# bias_supply.net
KiCad netlist of a schematic drawn in Altium Designer
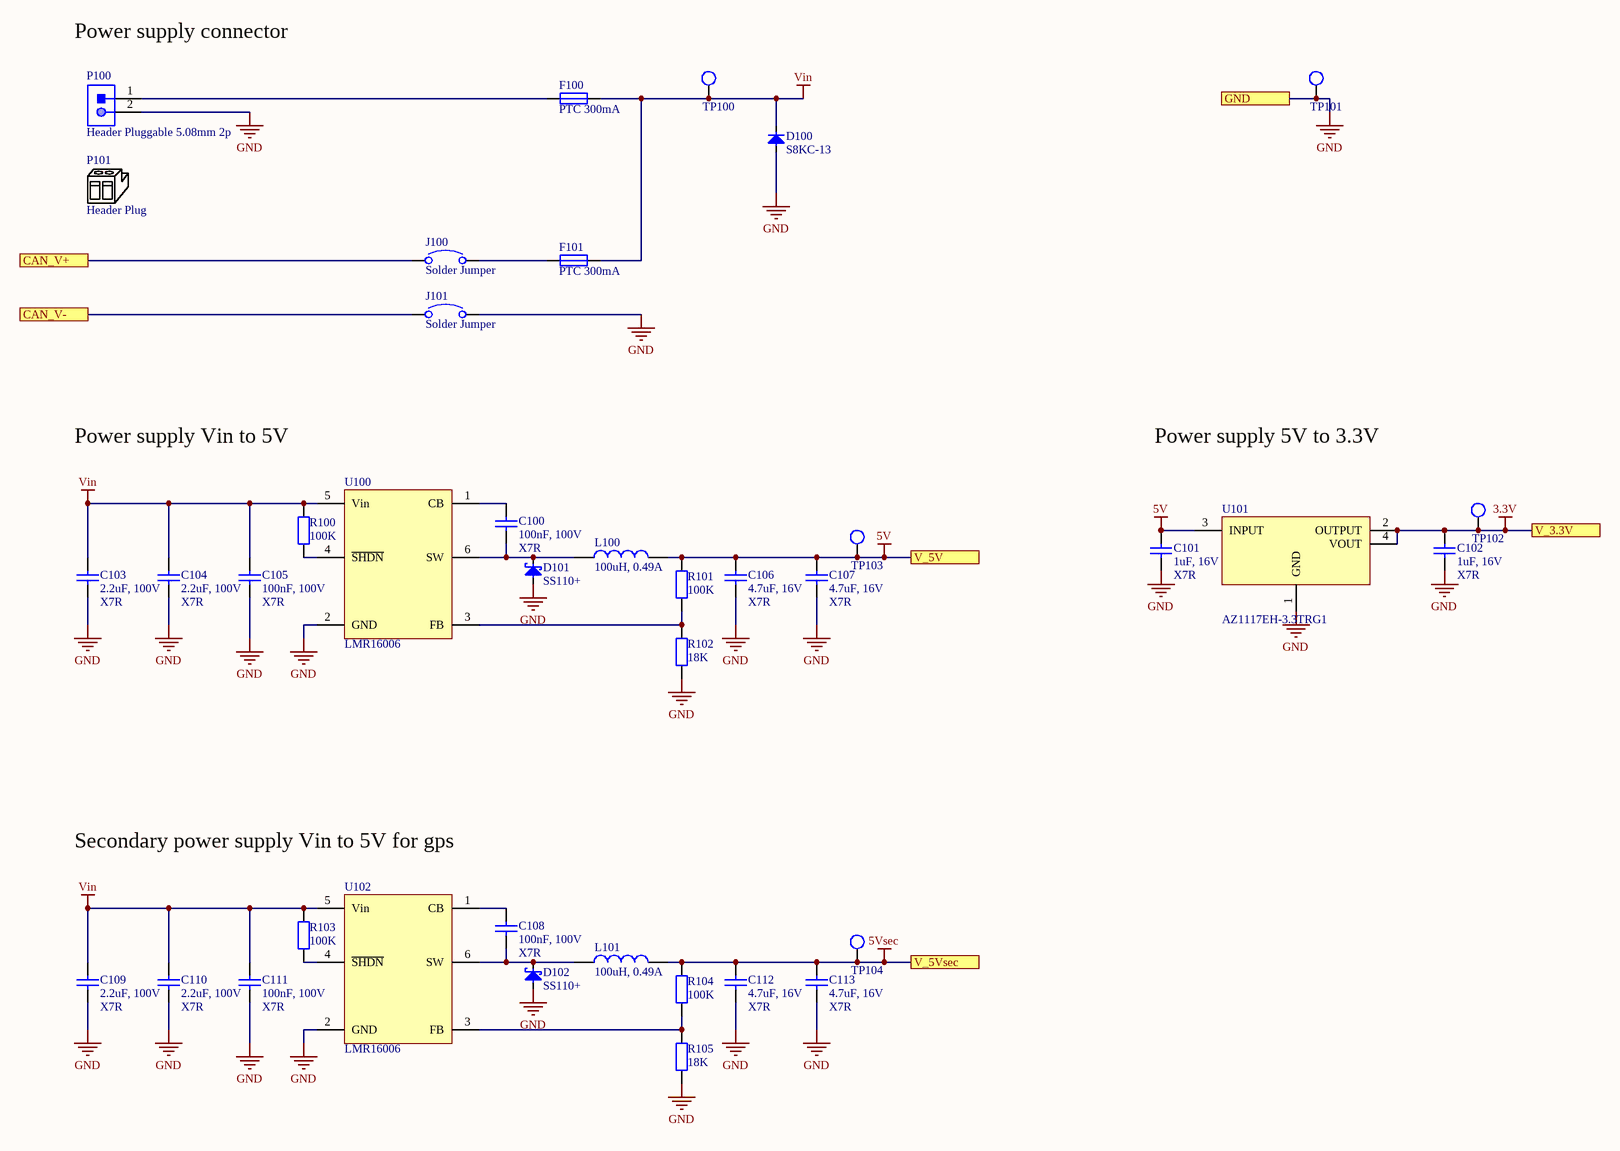
[diagram p0: bias supply.SchDoc]

(export (version "E")
  (design (tool "Eeschema 10.0.6"))
  (components
    (comp (ref "C100")
      (value "100nF, 100V")
      (footprint "CAP_0805")
      (description "WCAP-CSGP Multilayer Ceramic Chip Capacitor, General Purpose, size 0805, X7R, 100nF, 100V")
      (fields
        (field (name "MANUFACTURER PART NUMBER") "885012207128")
        (field (name "MANUFACTURER") "Wurth Elektronik")
        (field (name "CERAMIC TYPE") "X7R")
      )
      (libsource (lib "004-H-01 SD data logger") (part "CAP_0805_100nF_100V"))
    )
    (comp (ref "C101")
      (value "1uF, 16V")
      (footprint "CAP_0805")
      (description "WCAP-CSGP Multilayer Ceramic Chip Capacitor, General Purpose, size 0805, X7R, 1uF, 16V")
      (fields
        (field (name "MANUFACTURER PART NUMBER") "885012207051")
        (field (name "MANUFACTURER") "Wurth Elektronik")
        (field (name "CERAMIC TYPE") "X7R")
      )
      (libsource (lib "004-H-01 SD data logger") (part "CAP_0805_1uF_16V"))
    )
    (comp (ref "C102")
      (value "1uF, 16V")
      (footprint "CAP_0805")
      (description "WCAP-CSGP Multilayer Ceramic Chip Capacitor, General Purpose, size 0805, X7R, 1uF, 16V")
      (fields
        (field (name "MANUFACTURER PART NUMBER") "885012207051")
        (field (name "MANUFACTURER") "Wurth Elektronik")
        (field (name "CERAMIC TYPE") "X7R")
      )
      (libsource (lib "004-H-01 SD data logger") (part "CAP_0805_1uF_16V"))
    )
    (comp (ref "C103")
      (value "2.2uF, 100V")
      (footprint "CAP_1210")
      (description "WCAP-CSGP Multilayer Ceramic Chip Capacitor, General Purpose, size 1210, X7R, 2.2uF, 100V")
      (fields
        (field (name "MANUFACTURER PART NUMBER") "885012209071")
        (field (name "MANUFACTURER") "Wurth Elektronik")
        (field (name "CERAMIC TYPE") "X7R")
      )
      (libsource (lib "004-H-01 SD data logger") (part "CAP_1210_2.2uF_100V"))
    )
    (comp (ref "C104")
      (value "2.2uF, 100V")
      (footprint "CAP_1210")
      (description "WCAP-CSGP Multilayer Ceramic Chip Capacitor, General Purpose, size 1210, X7R, 2.2uF, 100V")
      (fields
        (field (name "MANUFACTURER PART NUMBER") "885012209071")
        (field (name "MANUFACTURER") "Wurth Elektronik")
        (field (name "CERAMIC TYPE") "X7R")
      )
      (libsource (lib "004-H-01 SD data logger") (part "CAP_1210_2.2uF_100V"))
    )
    (comp (ref "C105")
      (value "100nF, 100V")
      (footprint "CAP_0805")
      (description "WCAP-CSGP Multilayer Ceramic Chip Capacitor, General Purpose, size 0805, X7R, 100nF, 100V")
      (fields
        (field (name "MANUFACTURER PART NUMBER") "885012207128")
        (field (name "MANUFACTURER") "Wurth Elektronik")
        (field (name "CERAMIC TYPE") "X7R")
      )
      (libsource (lib "004-H-01 SD data logger") (part "CAP_0805_100nF_100V"))
    )
    (comp (ref "C106")
      (value "4.7uF, 16V")
      (footprint "CAP_0805")
      (description "WCAP-CSGP Multilayer Ceramic Chip Capacitor, General Purpose, size 0805, X7R, 4.7uF, 16V")
      (fields
        (field (name "MANUFACTURER PART NUMBER") "885012207053")
        (field (name "MANUFACTURER") "Wurth Elektronik")
        (field (name "CERAMIC TYPE") "X7R")
      )
      (libsource (lib "004-H-01 SD data logger") (part "CAP_0805_4.7uF_16V"))
    )
    (comp (ref "C107")
      (value "4.7uF, 16V")
      (footprint "CAP_0805")
      (description "WCAP-CSGP Multilayer Ceramic Chip Capacitor, General Purpose, size 0805, X7R, 4.7uF, 16V")
      (fields
        (field (name "MANUFACTURER PART NUMBER") "885012207053")
        (field (name "MANUFACTURER") "Wurth Elektronik")
        (field (name "CERAMIC TYPE") "X7R")
      )
      (libsource (lib "004-H-01 SD data logger") (part "CAP_0805_4.7uF_16V"))
    )
    (comp (ref "C108")
      (value "100nF, 100V")
      (footprint "CAP_0805")
      (description "WCAP-CSGP Multilayer Ceramic Chip Capacitor, General Purpose, size 0805, X7R, 100nF, 100V")
      (fields
        (field (name "MANUFACTURER PART NUMBER") "885012207128")
        (field (name "MANUFACTURER") "Wurth Elektronik")
        (field (name "CERAMIC TYPE") "X7R")
      )
      (libsource (lib "004-H-01 SD data logger") (part "CAP_0805_100nF_100V"))
    )
    (comp (ref "C109")
      (value "2.2uF, 100V")
      (footprint "CAP_1210")
      (description "WCAP-CSGP Multilayer Ceramic Chip Capacitor, General Purpose, size 1210, X7R, 2.2uF, 100V")
      (fields
        (field (name "MANUFACTURER PART NUMBER") "885012209071")
        (field (name "MANUFACTURER") "Wurth Elektronik")
        (field (name "CERAMIC TYPE") "X7R")
      )
      (libsource (lib "004-H-01 SD data logger") (part "CAP_1210_2.2uF_100V"))
    )
    (comp (ref "C110")
      (value "2.2uF, 100V")
      (footprint "CAP_1210")
      (description "WCAP-CSGP Multilayer Ceramic Chip Capacitor, General Purpose, size 1210, X7R, 2.2uF, 100V")
      (fields
        (field (name "MANUFACTURER PART NUMBER") "885012209071")
        (field (name "MANUFACTURER") "Wurth Elektronik")
        (field (name "CERAMIC TYPE") "X7R")
      )
      (libsource (lib "004-H-01 SD data logger") (part "CAP_1210_2.2uF_100V"))
    )
    (comp (ref "C111")
      (value "100nF, 100V")
      (footprint "CAP_0805")
      (description "WCAP-CSGP Multilayer Ceramic Chip Capacitor, General Purpose, size 0805, X7R, 100nF, 100V")
      (fields
        (field (name "MANUFACTURER PART NUMBER") "885012207128")
        (field (name "MANUFACTURER") "Wurth Elektronik")
        (field (name "CERAMIC TYPE") "X7R")
      )
      (libsource (lib "004-H-01 SD data logger") (part "CAP_0805_100nF_100V"))
    )
    (comp (ref "C112")
      (value "4.7uF, 16V")
      (footprint "CAP_0805")
      (description "WCAP-CSGP Multilayer Ceramic Chip Capacitor, General Purpose, size 0805, X7R, 4.7uF, 16V")
      (fields
        (field (name "MANUFACTURER PART NUMBER") "885012207053")
        (field (name "MANUFACTURER") "Wurth Elektronik")
        (field (name "CERAMIC TYPE") "X7R")
      )
      (libsource (lib "004-H-01 SD data logger") (part "CAP_0805_4.7uF_16V"))
    )
    (comp (ref "C113")
      (value "4.7uF, 16V")
      (footprint "CAP_0805")
      (description "WCAP-CSGP Multilayer Ceramic Chip Capacitor, General Purpose, size 0805, X7R, 4.7uF, 16V")
      (fields
        (field (name "MANUFACTURER PART NUMBER") "885012207053")
        (field (name "MANUFACTURER") "Wurth Elektronik")
        (field (name "CERAMIC TYPE") "X7R")
      )
      (libsource (lib "004-H-01 SD data logger") (part "CAP_0805_4.7uF_16V"))
    )
    (comp (ref "D100")
      (value "S8KC-13")
      (footprint "DIODEDO-214AB")
      (description "Diode")
      (fields (field (name "MANUFACTURER") "Diodes inc"))
      (libsource (lib "004-H-01 SD data logger") (part "Diode S8KC-13"))
    )
    (comp (ref "D101")
      (value "SS110+")
      (footprint "DIODEDO-214AC")
      (description "Diode Schottky")
      (fields (field (name "MANUFACTURER") "Multicomp"))
      (libsource (lib "004-H-01 SD data logger") (part "Diode Schottky SS110+"))
    )
    (comp (ref "D102")
      (value "SS110+")
      (footprint "DIODEDO-214AC")
      (description "Diode Schottky")
      (fields (field (name "MANUFACTURER") "Multicomp"))
      (libsource (lib "004-H-01 SD data logger") (part "Diode Schottky SS110+"))
    )
    (comp (ref "F100")
      (value "PTC 300mA")
      (footprint "PTC7451X12N")
      (description "Fuse")
      (fields (field (name "MANUFACTURER") "Multicomp Pro") (field (name "MANUFACTURER PART NO") "MC33189"))
      (libsource (lib "004-H-01 SD data logger") (part "PTC 300mA"))
    )
    (comp (ref "F101")
      (value "PTC 300mA")
      (footprint "PTC7451X12N")
      (description "Fuse")
      (fields (field (name "MANUFACTURER") "Multicomp Pro") (field (name "MANUFACTURER PART NO") "MC33189"))
      (libsource (lib "004-H-01 SD data logger") (part "PTC 300mA"))
    )
    (comp (ref "J100")
      (value "Solder Jumper")
      (footprint "SolderJumer")
      (description "Solder jumper open")
      (libsource (lib "004-H-01 SD data logger") (part "SolderJumper"))
    )
    (comp (ref "J101")
      (value "Solder Jumper")
      (footprint "SolderJumer")
      (description "Solder jumper open")
      (libsource (lib "004-H-01 SD data logger") (part "SolderJumper"))
    )
    (comp (ref "L100")
      (value "100uH, 0.49A")
      (footprint "WE-LQS_4025")
      (description "WE-LQS SMT Power Inductor, size 4025, 100uH, 0.49A")
      (fields
        (field (name "MANUFACTURER") "Wurth Elektronik")
        (field (name "MANUFACTURER PART NUMBER") "74404043101A")
      )
      (libsource (lib "004-H-01 SD data logger") (part "Inductor 100uH 0.49A 1043mOhm"))
    )
    (comp (ref "L101")
      (value "100uH, 0.49A")
      (footprint "WE-LQS_4025")
      (description "WE-LQS SMT Power Inductor, size 4025, 100uH, 0.49A")
      (fields
        (field (name "MANUFACTURER") "Wurth Elektronik")
        (field (name "MANUFACTURER PART NUMBER") "74404043101A")
      )
      (libsource (lib "004-H-01 SD data logger") (part "Inductor 100uH 0.49A 1043mOhm"))
    )
    (comp (ref "P100")
      (value "Header Pluggable 5.08mm 2p")
      (footprint "WE-691313510002")
      (description "WR-TBL Serie 313 Close Horizontal PCB Header, Pluggable, pitch 5.08mm, 2p")
      (fields (field (name "PART NUMBER") "691313510002") (field (name "PUBLISHER") "Wurth Elektronik"))
      (libsource (lib "004-H-01 SD data logger") (part "Header Pluggable 5.08mm 2p"))
    )
    (comp (ref "P101")
      (value "Header Plug")
      (description "WR-TBL Series 351 - 5.08 mm Vertical, pitch 5.08mm, 2p")
      (fields (field (name "PART NUMBER") "691351500002") (field (name "PUBLISHER") "Wurth Elektronik"))
      (libsource (lib "004-H-01 SD data logger") (part "Plug Pluggable 5.08mm 2p"))
    )
    (comp (ref "R100")
      (value "100K")
      (footprint "RES_0805")
      (description "Thick Film Resistor, size 0805, 1%")
      (libsource (lib "004-H-01 SD data logger") (part "RES_0805_100K"))
    )
    (comp (ref "R101")
      (value "100K")
      (footprint "RES_0805")
      (description "Thick Film Resistor, size 0805, 1%")
      (libsource (lib "004-H-01 SD data logger") (part "RES_0805_100K"))
    )
    (comp (ref "R102")
      (value "18K")
      (footprint "RES_0805")
      (description "Thick Film Resistor, size 0805, 1%")
      (libsource (lib "004-H-01 SD data logger") (part "RES_0805_18K"))
    )
    (comp (ref "R103")
      (value "100K")
      (footprint "RES_0805")
      (description "Thick Film Resistor, size 0805, 1%")
      (libsource (lib "004-H-01 SD data logger") (part "RES_0805_100K"))
    )
    (comp (ref "R104")
      (value "100K")
      (footprint "RES_0805")
      (description "Thick Film Resistor, size 0805, 1%")
      (libsource (lib "004-H-01 SD data logger") (part "RES_0805_100K"))
    )
    (comp (ref "R105")
      (value "18K")
      (footprint "RES_0805")
      (description "Thick Film Resistor, size 0805, 1%")
      (libsource (lib "004-H-01 SD data logger") (part "RES_0805_18K"))
    )
    (comp (ref "TP100")
      (value "Test Pad")
      (footprint "TestPad")
      (description "Test pad 2mm")
      (libsource (lib "004-H-01 SD data logger") (part "Test Pad"))
    )
    (comp (ref "TP101")
      (value "Test Pad")
      (footprint "TestPad")
      (description "Test pad 2mm")
      (libsource (lib "004-H-01 SD data logger") (part "Test Pad"))
    )
    (comp (ref "TP102")
      (value "Test Pad")
      (footprint "TestPad")
      (description "Test pad 2mm")
      (libsource (lib "004-H-01 SD data logger") (part "Test Pad"))
    )
    (comp (ref "TP103")
      (value "Test Pad")
      (footprint "TestPad")
      (description "Test pad 2mm")
      (libsource (lib "004-H-01 SD data logger") (part "Test Pad"))
    )
    (comp (ref "TP104")
      (value "Test Pad")
      (footprint "TestPad")
      (description "Test pad 2mm")
      (libsource (lib "004-H-01 SD data logger") (part "Test Pad"))
    )
    (comp (ref "U100")
      (value "LMR16006")
      (footprint "SOT95P280X110-6N")
      (fields
        (field (name "MANUFACTURER") "Texas Instruments")
        (field (name "MANUFACTURER PART NO") "LMR16006XDDCT")
      )
      (libsource (lib "004-H-01 SD data logger") (part "LMR16006"))
    )
    (comp (ref "U101")
      (value "AZ1117EH-3.3TRG1")
      (footprint "FP-SOT223-IPC_A")
      (description "IC REG LINEAR 3.3V 1A SOT223")
      (fields (field (name "MANUFACTURER") "Diodes Inc"))
      (libsource (lib "004-H-01 SD data logger") (part "AZ1117EH-3.3TRG1"))
    )
    (comp (ref "U102")
      (value "LMR16006")
      (footprint "SOT95P280X110-6N")
      (fields
        (field (name "MANUFACTURER") "Texas Instruments")
        (field (name "MANUFACTURER PART NO") "LMR16006XDDCT")
      )
      (libsource (lib "004-H-01 SD data logger") (part "LMR16006"))
    )
  )
  (nets
    (net (code "1") (name "/CAN_V+") (class "Default")
      (node (ref "J100") (pin "1") (pinfunction "1_1") (pintype "passive"))
    )
    (net (code "2") (name "/CAN_V-") (class "Default")
      (node (ref "J101") (pin "1") (pinfunction "1_1") (pintype "passive"))
    )
    (net (code "3") (name "3.3V") (class "Default")
      (node (ref "C102") (pin "1") (pinfunction "1_1") (pintype "passive"))
      (node (ref "TP102") (pin "1") (pinfunction "1_1") (pintype "passive"))
      (node (ref "U101") (pin "2") (pinfunction "OUTPUT_2") (pintype "power_in"))
      (node (ref "U101") (pin "4") (pinfunction "VOUT_4") (pintype "power_in"))
    )
    (net (code "4") (name "5V") (class "Default")
      (node (ref "C101") (pin "2") (pinfunction "2_2") (pintype "passive"))
      (node (ref "C106") (pin "2") (pinfunction "2_2") (pintype "passive"))
      (node (ref "C107") (pin "1") (pinfunction "1_1") (pintype "passive"))
      (node (ref "L100") (pin "2") (pinfunction "2_2") (pintype "passive"))
      (node (ref "R101") (pin "2") (pinfunction "2_2") (pintype "passive"))
      (node (ref "TP103") (pin "1") (pinfunction "1_1") (pintype "passive"))
      (node (ref "U101") (pin "3") (pinfunction "INPUT_3") (pintype "power_in"))
    )
    (net (code "5") (name "5Vsec") (class "Default")
      (node (ref "C112") (pin "2") (pinfunction "2_2") (pintype "passive"))
      (node (ref "C113") (pin "1") (pinfunction "1_1") (pintype "passive"))
      (node (ref "L101") (pin "2") (pinfunction "2_2") (pintype "passive"))
      (node (ref "R104") (pin "2") (pinfunction "2_2") (pintype "passive"))
      (node (ref "TP104") (pin "1") (pinfunction "1_1") (pintype "passive"))
    )
    (net (code "6") (name "GND") (class "Default")
      (node (ref "C101") (pin "1") (pinfunction "1_1") (pintype "passive"))
      (node (ref "C102") (pin "2") (pinfunction "2_2") (pintype "passive"))
      (node (ref "C103") (pin "1") (pinfunction "1_1") (pintype "passive"))
      (node (ref "C104") (pin "2") (pinfunction "2_2") (pintype "passive"))
      (node (ref "C105") (pin "1") (pinfunction "1_1") (pintype "passive"))
      (node (ref "C106") (pin "1") (pinfunction "1_1") (pintype "passive"))
      (node (ref "C107") (pin "2") (pinfunction "2_2") (pintype "passive"))
      (node (ref "C109") (pin "1") (pinfunction "1_1") (pintype "passive"))
      (node (ref "C110") (pin "2") (pinfunction "2_2") (pintype "passive"))
      (node (ref "C111") (pin "1") (pinfunction "1_1") (pintype "passive"))
      (node (ref "C112") (pin "1") (pinfunction "1_1") (pintype "passive"))
      (node (ref "C113") (pin "2") (pinfunction "2_2") (pintype "passive"))
      (node (ref "D100") (pin "2") (pinfunction "A_2") (pintype "passive"))
      (node (ref "D101") (pin "2") (pinfunction "A_2") (pintype "passive"))
      (node (ref "D102") (pin "2") (pinfunction "A_2") (pintype "passive"))
      (node (ref "J101") (pin "2") (pinfunction "2_2") (pintype "passive"))
      (node (ref "P100") (pin "2") (pinfunction "2_2") (pintype "passive"))
      (node (ref "R102") (pin "1") (pinfunction "1_1") (pintype "passive"))
      (node (ref "R105") (pin "1") (pinfunction "1_1") (pintype "passive"))
      (node (ref "TP101") (pin "1") (pinfunction "1_1") (pintype "passive"))
      (node (ref "U100") (pin "2") (pinfunction "GND_2") (pintype "passive"))
      (node (ref "U101") (pin "1") (pinfunction "GND_1") (pintype "power_in"))
      (node (ref "U102") (pin "2") (pinfunction "GND_2") (pintype "passive"))
    )
    (net (code "7") (name "Net-(D101-K)") (class "Default")
      (node (ref "C100") (pin "2") (pinfunction "2_2") (pintype "passive"))
      (node (ref "D101") (pin "1") (pinfunction "K_1") (pintype "passive"))
      (node (ref "L100") (pin "1") (pinfunction "1_1") (pintype "passive"))
      (node (ref "U100") (pin "6") (pinfunction "SW_6") (pintype "passive"))
    )
    (net (code "8") (name "Net-(D102-K)") (class "Default")
      (node (ref "C108") (pin "2") (pinfunction "2_2") (pintype "passive"))
      (node (ref "D102") (pin "1") (pinfunction "K_1") (pintype "passive"))
      (node (ref "L101") (pin "1") (pinfunction "1_1") (pintype "passive"))
      (node (ref "U102") (pin "6") (pinfunction "SW_6") (pintype "passive"))
    )
    (net (code "9") (name "Net-(F100-Pad1)") (class "Default")
      (node (ref "F100") (pin "1") (pinfunction "1_1") (pintype "passive"))
      (node (ref "P100") (pin "1") (pinfunction "1_1") (pintype "passive"))
    )
    (net (code "10") (name "Net-(F101-Pad1)") (class "Default")
      (node (ref "F101") (pin "1") (pinfunction "1_1") (pintype "passive"))
      (node (ref "J100") (pin "2") (pinfunction "2_2") (pintype "passive"))
    )
    (net (code "11") (name "Net-(U100-CB)") (class "Default")
      (node (ref "C100") (pin "1") (pinfunction "1_1") (pintype "passive"))
      (node (ref "U100") (pin "1") (pinfunction "CB_1") (pintype "passive"))
    )
    (net (code "12") (name "Net-(U100-FB)") (class "Default")
      (node (ref "R101") (pin "1") (pinfunction "1_1") (pintype "passive"))
      (node (ref "R102") (pin "2") (pinfunction "2_2") (pintype "passive"))
      (node (ref "U100") (pin "3") (pinfunction "FB_3") (pintype "passive"))
    )
    (net (code "13") (name "Net-(U100-~{SHDN})") (class "Default")
      (node (ref "R100") (pin "1") (pinfunction "1_1") (pintype "passive"))
      (node (ref "U100") (pin "4") (pinfunction "~{SHDN}_4") (pintype "passive"))
    )
    (net (code "14") (name "Net-(U102-CB)") (class "Default")
      (node (ref "C108") (pin "1") (pinfunction "1_1") (pintype "passive"))
      (node (ref "U102") (pin "1") (pinfunction "CB_1") (pintype "passive"))
    )
    (net (code "15") (name "Net-(U102-FB)") (class "Default")
      (node (ref "R104") (pin "1") (pinfunction "1_1") (pintype "passive"))
      (node (ref "R105") (pin "2") (pinfunction "2_2") (pintype "passive"))
      (node (ref "U102") (pin "3") (pinfunction "FB_3") (pintype "passive"))
    )
    (net (code "16") (name "Net-(U102-~{SHDN})") (class "Default")
      (node (ref "R103") (pin "1") (pinfunction "1_1") (pintype "passive"))
      (node (ref "U102") (pin "4") (pinfunction "~{SHDN}_4") (pintype "passive"))
    )
    (net (code "17") (name "Vin") (class "Default")
      (node (ref "C103") (pin "2") (pinfunction "2_2") (pintype "passive"))
      (node (ref "C104") (pin "1") (pinfunction "1_1") (pintype "passive"))
      (node (ref "C105") (pin "2") (pinfunction "2_2") (pintype "passive"))
      (node (ref "C109") (pin "2") (pinfunction "2_2") (pintype "passive"))
      (node (ref "C110") (pin "1") (pinfunction "1_1") (pintype "passive"))
      (node (ref "C111") (pin "2") (pinfunction "2_2") (pintype "passive"))
      (node (ref "D100") (pin "1") (pinfunction "K_1") (pintype "passive"))
      (node (ref "F100") (pin "2") (pinfunction "2_2") (pintype "passive"))
      (node (ref "F101") (pin "2") (pinfunction "2_2") (pintype "passive"))
      (node (ref "R100") (pin "2") (pinfunction "2_2") (pintype "passive"))
      (node (ref "R103") (pin "2") (pinfunction "2_2") (pintype "passive"))
      (node (ref "TP100") (pin "1") (pinfunction "1_1") (pintype "passive"))
      (node (ref "U100") (pin "5") (pinfunction "Vin_5") (pintype "passive"))
      (node (ref "U102") (pin "5") (pinfunction "Vin_5") (pintype "passive"))
    )
  )
)
